# 07_-_HDMI.net
KiCad netlist of a schematic drawn in Altium Designer
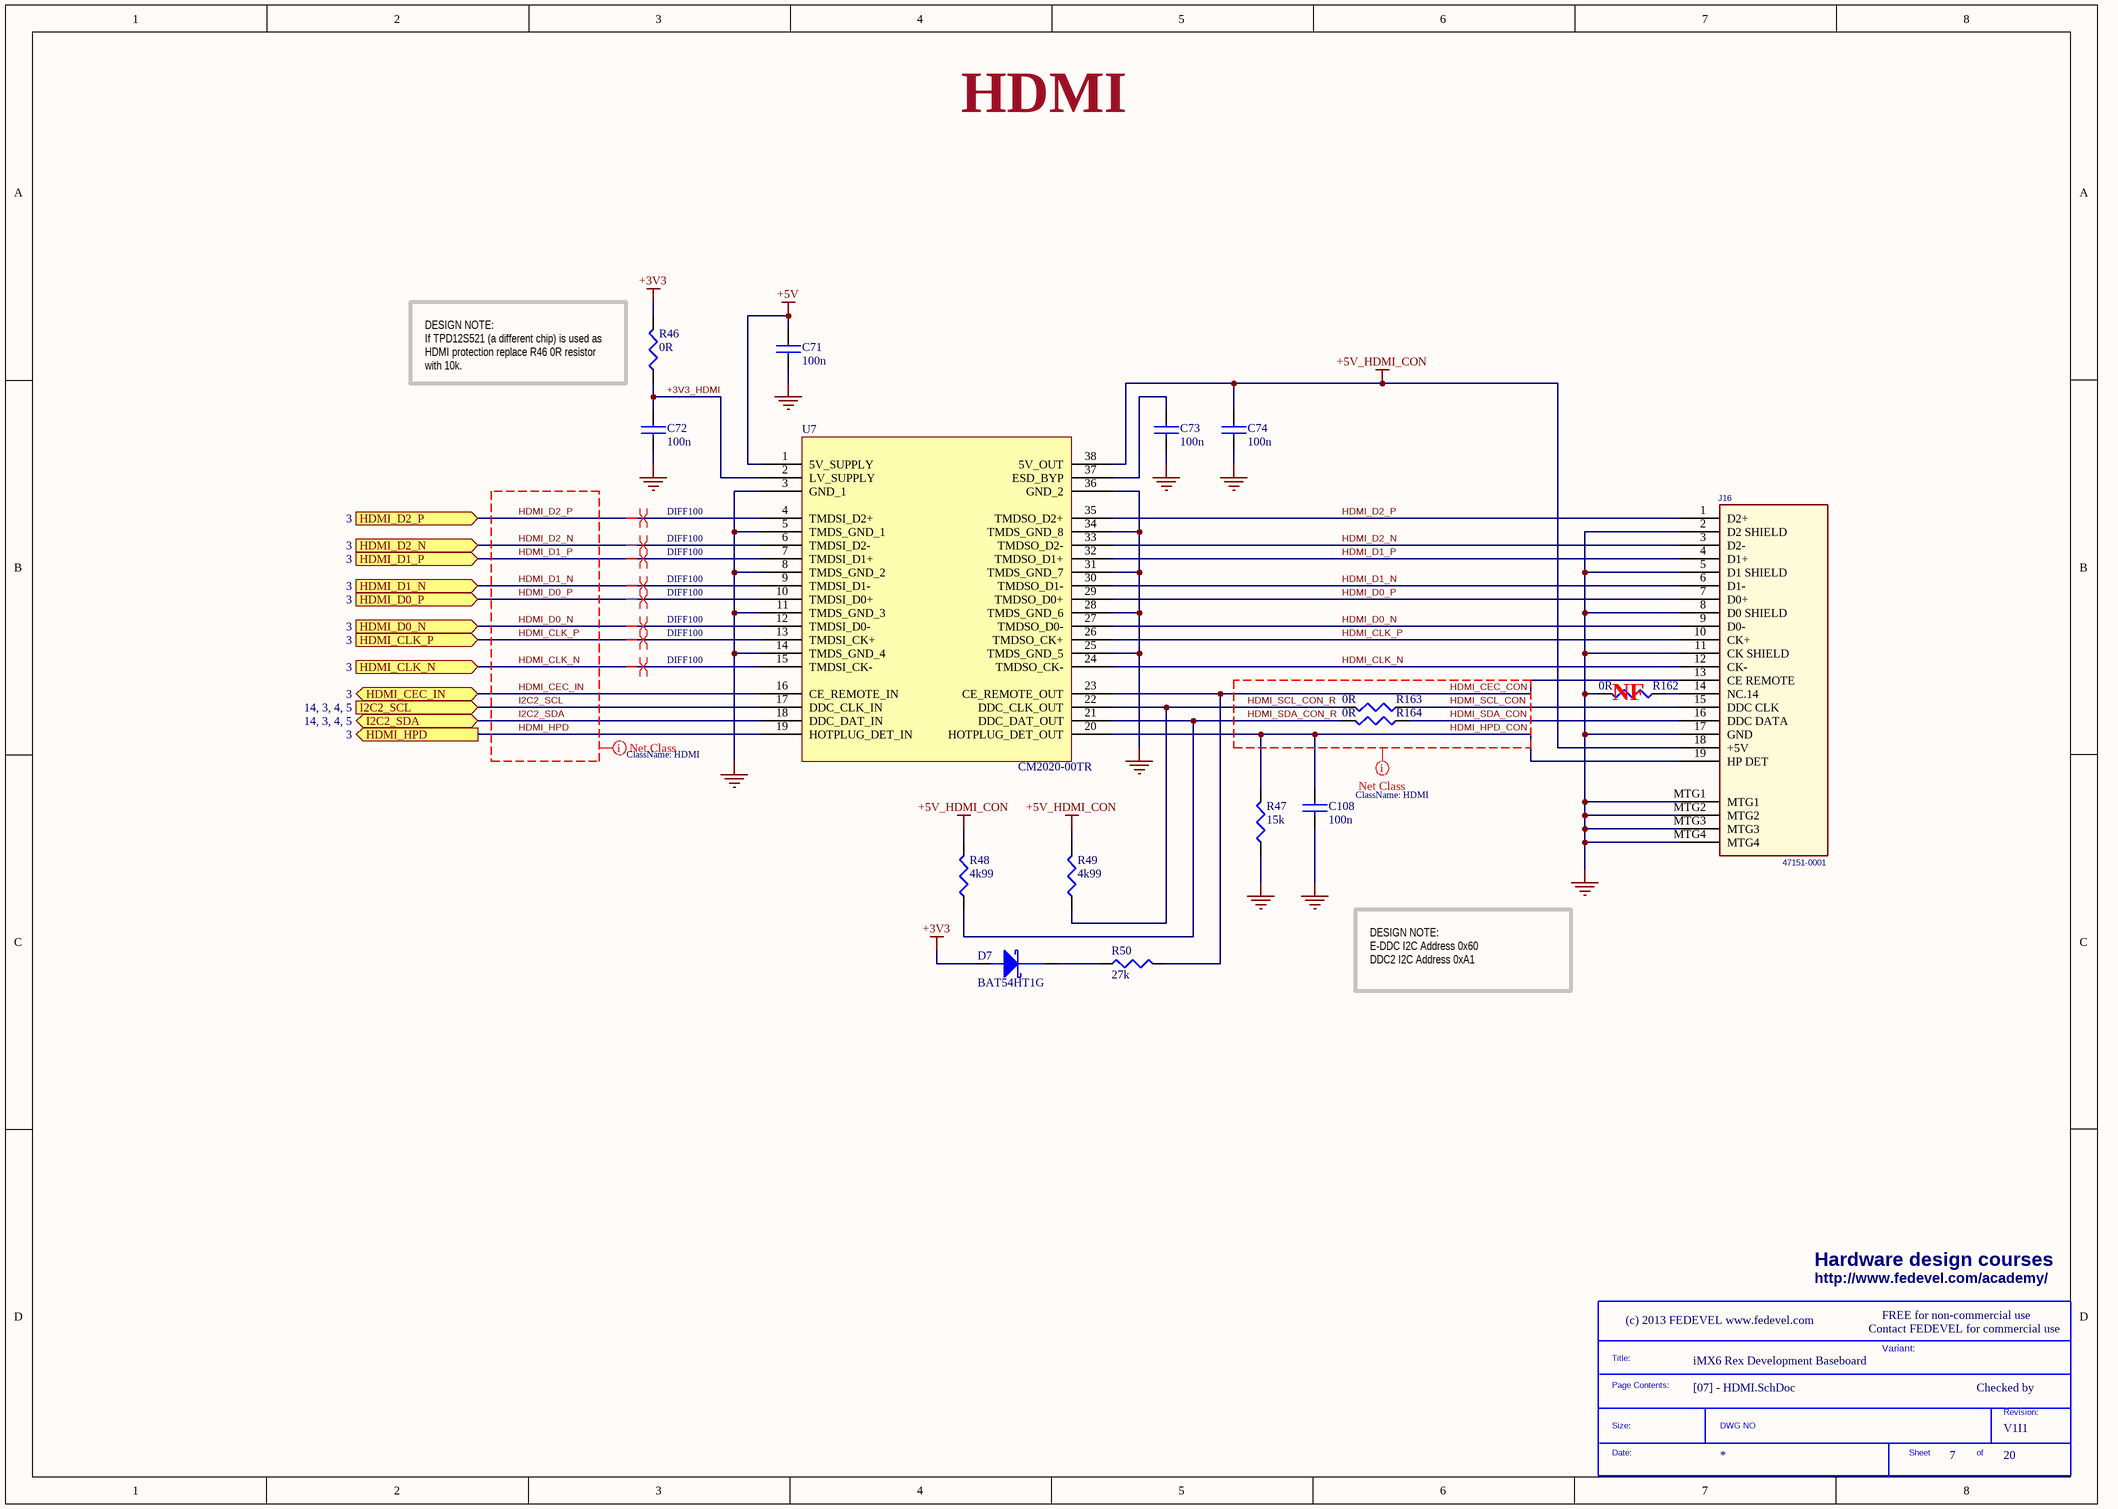
[diagram p0: [07] - HDMI.SchDoc]

(export (version "E")
  (design (tool "Eeschema 10.0.6"))
  (components
    (comp (ref "C71")
      (value "100n")
      (footprint "C0402")
      (description "CAP CER .10UF 50V X5R 10% 0402")
      (fields
        (field (name "MANUFACTURER") "TDK Corporation")
        (field (name "MANUFACTURER PART NUMBER") "C1005X5R1H104K")
      )
      (libsource (lib "Integrated_Library_RF_FEB_2012") (part "C1005X5R1H104K"))
    )
    (comp (ref "C72")
      (value "100n")
      (footprint "C0402")
      (description "CAP CER .10UF 50V X5R 10% 0402")
      (fields
        (field (name "MANUFACTURER") "TDK Corporation")
        (field (name "MANUFACTURER PART NUMBER") "C1005X5R1H104K")
      )
      (libsource (lib "Integrated_Library_RF_FEB_2012") (part "C1005X5R1H104K"))
    )
    (comp (ref "C73")
      (value "100n")
      (footprint "C0402")
      (description "CAP CER .10UF 50V X5R 10% 0402")
      (fields
        (field (name "MANUFACTURER") "TDK Corporation")
        (field (name "MANUFACTURER PART NUMBER") "C1005X5R1H104K")
      )
      (libsource (lib "Integrated_Library_RF_FEB_2012") (part "C1005X5R1H104K"))
    )
    (comp (ref "C74")
      (value "100n")
      (footprint "C0402")
      (description "CAP CER .10UF 50V X5R 10% 0402")
      (fields
        (field (name "MANUFACTURER") "TDK Corporation")
        (field (name "MANUFACTURER PART NUMBER") "C1005X5R1H104K")
      )
      (libsource (lib "Integrated_Library_RF_FEB_2012") (part "C1005X5R1H104K"))
    )
    (comp (ref "C108")
      (value "100n")
      (footprint "C0402")
      (description "CAP CER .10UF 50V X5R 10% 0402")
      (fields
        (field (name "MANUFACTURER") "TDK Corporation")
        (field (name "MANUFACTURER PART NUMBER") "C1005X5R1H104K")
      )
      (libsource (lib "Integrated_Library_RF_FEB_2012") (part "C1005X5R1H104K"))
    )
    (comp (ref "D7")
      (value "BAT54HT1G")
      (footprint "SOD323")
      (description "DIODE SCHOTTKY 30V 0.2A SOD323")
      (fields
        (field (name "MANUFACTURER") "Fairchild Semiconductor")
        (field (name ".CREATOR") "MM")
        (field (name ".CHECKED PCB") "RF, used by MM")
        (field (name ".CHECKED SCH") "MM")
      )
      (libsource (lib "Integrated_Library_RF_FEB_2012") (part "BAT54HT1G"))
    )
    (comp (ref "J16")
      (value "47151-0001")
      (footprint "HDMI")
      (description "CONN RCPT 19POS HDMI RT ANG SMD")
      (fields (field (name "MANUFACTURER") "Molex Connector Corporation"))
      (libsource (lib "Integrated_Library_RF_FEB_2012") (part "47151-0001"))
    )
    (comp (ref "R46")
      (value "0R")
      (footprint "R0402")
      (description "RES 0.0 OHM 1/16W 0402 SMD")
      (fields
        (field (name "MANUFACTURER") "Yageo")
        (field (name "MANUFACTURER PART NUMBER") "RC0402JR-070RL")
      )
      (libsource (lib "Integrated_Library_RF_FEB_2012") (part "RC0402JR-070RL"))
    )
    (comp (ref "R47")
      (value "15k")
      (footprint "R0402")
      (description "RES 15.0K OHM 1/16W 1% 0402 SMD")
      (fields
        (field (name "MANUFACTURER") "Yageo")
        (field (name "MANUFACTURER PART NUMBER") "RC0402FR-0715KL")
      )
      (libsource (lib "Integrated_Library_RF_FEB_2012") (part "RC0402FR-0715KL"))
    )
    (comp (ref "R48")
      (value "4k99")
      (footprint "R0402")
      (description "RES TF 4.99K OHM 1% 1/16W 0402")
      (fields
        (field (name "MANUFACTURER") "Stackpole Electronics Inc")
        (field (name "MANUFACTURER PART NUMBER") "RMCF0402FT4K99")
      )
      (libsource (lib "Integrated_Library_RF_FEB_2012") (part "RMCF0402FT4K99"))
    )
    (comp (ref "R49")
      (value "4k99")
      (footprint "R0402")
      (description "RES TF 4.99K OHM 1% 1/16W 0402")
      (fields
        (field (name "MANUFACTURER") "Stackpole Electronics Inc")
        (field (name "MANUFACTURER PART NUMBER") "RMCF0402FT4K99")
      )
      (libsource (lib "Integrated_Library_RF_FEB_2012") (part "RMCF0402FT4K99"))
    )
    (comp (ref "R50")
      (value "27k")
      (footprint "R0402")
      (description "RES 27.0K OHM 1/16W 1% 0402 SMD")
      (fields
        (field (name "MANUFACTURER") "Yageo")
        (field (name "MANUFACTURER PART NUMBER") "RC0402FR-0727KL")
        (field (name ".CHECKED PCB") "RF")
        (field (name ".CHECKED SCH") "RF")
      )
      (libsource (lib "Integrated_Library_RF_FEB_2012") (part "RC0402FR-0727KL"))
    )
    (comp (ref "R162")
      (value "0R")
      (footprint "R0402")
      (description "RES 0.0 OHM 1/16W 0402 SMD")
      (fields
        (field (name "MANUFACTURER") "Yageo")
        (field (name "MANUFACTURER PART NUMBER") "RC0402JR-070RL")
      )
      (libsource (lib "Integrated_Library_RF_FEB_2012") (part "RC0402JR-070RL"))
    )
    (comp (ref "R163")
      (value "0R")
      (footprint "R0402")
      (description "RES 0.0 OHM 1/16W 0402 SMD")
      (fields
        (field (name "MANUFACTURER") "Yageo")
        (field (name "MANUFACTURER PART NUMBER") "RC0402JR-070RL")
      )
      (libsource (lib "Integrated_Library_RF_FEB_2012") (part "RC0402JR-070RL"))
    )
    (comp (ref "R164")
      (value "0R")
      (footprint "R0402")
      (description "RES 0.0 OHM 1/16W 0402 SMD")
      (fields
        (field (name "MANUFACTURER") "Yageo")
        (field (name "MANUFACTURER PART NUMBER") "RC0402JR-070RL")
      )
      (libsource (lib "Integrated_Library_RF_FEB_2012") (part "RC0402JR-070RL"))
    )
    (comp (ref "U7")
      (value "CM2020-00TR")
      (footprint "TSSOP_38")
      (description "IC HDMI TX PORT P/I 38-TSSOP")
      (fields
        (field (name "MANUFACTURER") "ON Semiconductor")
        (field (name ".CREATOR") "MM")
        (field (name ".CHECKED PCB") "RF, used by MM")
        (field (name ".CHECKED SCH") "RF, used by MM")
      )
      (libsource (lib "Integrated_Library_RF_FEB_2012") (part "CM2020-00TR"))
    )
  )
  (nets
    (net (code "1") (name "+3V3") (class "Default")
      (node (ref "D7") (pin "2") (pinfunction "Anode_2") (pintype "passive"))
      (node (ref "R46") (pin "2") (pinfunction "2_2") (pintype "passive"))
    )
    (net (code "2") (name "+5V") (class "Default")
      (node (ref "C71") (pin "1") (pinfunction "1_1") (pintype "passive"))
      (node (ref "U7") (pin "1") (pinfunction "5V_SUPPLY_1") (pintype "passive"))
    )
    (net (code "3") (name "+5V_HDMI_CON") (class "Default")
      (node (ref "C74") (pin "1") (pinfunction "1_1") (pintype "passive"))
      (node (ref "J16") (pin "18") (pinfunction "+5V_18") (pintype "passive"))
      (node (ref "R48") (pin "2") (pinfunction "2_2") (pintype "passive"))
      (node (ref "R49") (pin "2") (pinfunction "2_2") (pintype "passive"))
      (node (ref "U7") (pin "38") (pinfunction "5V_OUT_38") (pintype "passive"))
    )
    (net (code "4") (name "/+3V3_HDMI") (class "Default")
      (node (ref "C72") (pin "1") (pinfunction "1_1") (pintype "passive"))
      (node (ref "R46") (pin "1") (pinfunction "1_1") (pintype "passive"))
      (node (ref "U7") (pin "2") (pinfunction "LV_SUPPLY_2") (pintype "passive"))
    )
    (net (code "5") (name "/HDMI_CEC_CON") (class "Default")
      (node (ref "J16") (pin "13") (pinfunction "CE_REMOTE_13") (pintype "passive"))
      (node (ref "R50") (pin "2") (pinfunction "2_2") (pintype "passive"))
      (node (ref "U7") (pin "23") (pinfunction "CE_REMOTE_OUT_23") (pintype "passive"))
    )
    (net (code "6") (name "/HDMI_CEC_IN") (class "Default")
      (node (ref "U7") (pin "16") (pinfunction "CE_REMOTE_IN_16") (pintype "passive"))
    )
    (net (code "7") (name "/HDMI_CLK_N") (class "Default")
      (node (ref "J16") (pin "12") (pinfunction "CK-_12") (pintype "passive"))
      (node (ref "U7") (pin "15") (pinfunction "TMDSI_CK-_15") (pintype "passive"))
      (node (ref "U7") (pin "24") (pinfunction "TMDSO_CK-_24") (pintype "passive"))
    )
    (net (code "8") (name "/HDMI_CLK_P") (class "Default")
      (node (ref "J16") (pin "10") (pinfunction "CK+_10") (pintype "passive"))
      (node (ref "U7") (pin "13") (pinfunction "TMDSI_CK+_13") (pintype "passive"))
      (node (ref "U7") (pin "26") (pinfunction "TMDSO_CK+_26") (pintype "passive"))
    )
    (net (code "9") (name "/HDMI_D0_N") (class "Default")
      (node (ref "J16") (pin "9") (pinfunction "D0-_9") (pintype "passive"))
      (node (ref "U7") (pin "12") (pinfunction "TMDSI_D0-_12") (pintype "passive"))
      (node (ref "U7") (pin "27") (pinfunction "TMDSO_D0-_27") (pintype "passive"))
    )
    (net (code "10") (name "/HDMI_D0_P") (class "Default")
      (node (ref "J16") (pin "7") (pinfunction "D0+_7") (pintype "passive"))
      (node (ref "U7") (pin "10") (pinfunction "TMDSI_D0+_10") (pintype "passive"))
      (node (ref "U7") (pin "29") (pinfunction "TMDSO_D0+_29") (pintype "passive"))
    )
    (net (code "11") (name "/HDMI_D1_N") (class "Default")
      (node (ref "J16") (pin "6") (pinfunction "D1-_6") (pintype "passive"))
      (node (ref "U7") (pin "30") (pinfunction "TMDSO_D1-_30") (pintype "passive"))
      (node (ref "U7") (pin "9") (pinfunction "TMDSI_D1-_9") (pintype "passive"))
    )
    (net (code "12") (name "/HDMI_D1_P") (class "Default")
      (node (ref "J16") (pin "4") (pinfunction "D1+_4") (pintype "passive"))
      (node (ref "U7") (pin "32") (pinfunction "TMDSO_D1+_32") (pintype "passive"))
      (node (ref "U7") (pin "7") (pinfunction "TMDSI_D1+_7") (pintype "passive"))
    )
    (net (code "13") (name "/HDMI_D2_N") (class "Default")
      (node (ref "J16") (pin "3") (pinfunction "D2-_3") (pintype "passive"))
      (node (ref "U7") (pin "33") (pinfunction "TMDSO_D2-_33") (pintype "passive"))
      (node (ref "U7") (pin "6") (pinfunction "TMDSI_D2-_6") (pintype "passive"))
    )
    (net (code "14") (name "/HDMI_D2_P") (class "Default")
      (node (ref "J16") (pin "1") (pinfunction "D2+_1") (pintype "passive"))
      (node (ref "U7") (pin "35") (pinfunction "TMDSO_D2+_35") (pintype "passive"))
      (node (ref "U7") (pin "4") (pinfunction "TMDSI_D2+_4") (pintype "passive"))
    )
    (net (code "15") (name "/HDMI_HPD") (class "Default")
      (node (ref "U7") (pin "19") (pinfunction "HOTPLUG_DET_IN_19") (pintype "passive"))
    )
    (net (code "16") (name "/HDMI_HPD_CON") (class "Default")
      (node (ref "C108") (pin "1") (pinfunction "1_1") (pintype "passive"))
      (node (ref "J16") (pin "19") (pinfunction "HP_DET_19") (pintype "passive"))
      (node (ref "R47") (pin "2") (pinfunction "2_2") (pintype "passive"))
      (node (ref "U7") (pin "20") (pinfunction "HOTPLUG_DET_OUT_20") (pintype "passive"))
    )
    (net (code "17") (name "/HDMI_SCL_CON") (class "Default")
      (node (ref "J16") (pin "15") (pinfunction "DDC_CLK_15") (pintype "passive"))
      (node (ref "R163") (pin "1") (pinfunction "1_1") (pintype "passive"))
    )
    (net (code "18") (name "/HDMI_SCL_CON_R") (class "Default")
      (node (ref "R163") (pin "2") (pinfunction "2_2") (pintype "passive"))
      (node (ref "R49") (pin "1") (pinfunction "1_1") (pintype "passive"))
      (node (ref "U7") (pin "22") (pinfunction "DDC_CLK_OUT_22") (pintype "passive"))
    )
    (net (code "19") (name "/HDMI_SDA_CON") (class "Default")
      (node (ref "J16") (pin "16") (pinfunction "DDC_DATA_16") (pintype "passive"))
      (node (ref "R164") (pin "1") (pinfunction "1_1") (pintype "passive"))
    )
    (net (code "20") (name "/HDMI_SDA_CON_R") (class "Default")
      (node (ref "R164") (pin "2") (pinfunction "2_2") (pintype "passive"))
      (node (ref "R48") (pin "1") (pinfunction "1_1") (pintype "passive"))
      (node (ref "U7") (pin "21") (pinfunction "DDC_DAT_OUT_21") (pintype "passive"))
    )
    (net (code "21") (name "/I2C2_SCL") (class "Default")
      (node (ref "U7") (pin "17") (pinfunction "DDC_CLK_IN_17") (pintype "passive"))
    )
    (net (code "22") (name "/I2C2_SDA") (class "Default")
      (node (ref "U7") (pin "18") (pinfunction "DDC_DAT_IN_18") (pintype "passive"))
    )
    (net (code "23") (name "GND") (class "Default")
      (node (ref "C108") (pin "2") (pinfunction "2_2") (pintype "passive"))
      (node (ref "C71") (pin "2") (pinfunction "2_2") (pintype "passive"))
      (node (ref "C72") (pin "2") (pinfunction "2_2") (pintype "passive"))
      (node (ref "C73") (pin "2") (pinfunction "2_2") (pintype "passive"))
      (node (ref "C74") (pin "2") (pinfunction "2_2") (pintype "passive"))
      (node (ref "J16") (pin "11") (pinfunction "CK_SHIELD_11") (pintype "passive"))
      (node (ref "J16") (pin "17") (pinfunction "GND_17") (pintype "passive"))
      (node (ref "J16") (pin "2") (pinfunction "D2_SHIELD_2") (pintype "passive"))
      (node (ref "J16") (pin "5") (pinfunction "D1_SHIELD_5") (pintype "passive"))
      (node (ref "J16") (pin "8") (pinfunction "D0_SHIELD_8") (pintype "passive"))
      (node (ref "J16") (pin "MTG1") (pinfunction "MTG1_MTG1") (pintype "passive"))
      (node (ref "J16") (pin "MTG2") (pinfunction "MTG2_MTG2") (pintype "passive"))
      (node (ref "J16") (pin "MTG3") (pinfunction "MTG3_MTG3") (pintype "passive"))
      (node (ref "J16") (pin "MTG4") (pinfunction "MTG4_MTG4") (pintype "passive"))
      (node (ref "R162") (pin "2") (pinfunction "2_2") (pintype "passive"))
      (node (ref "R47") (pin "1") (pinfunction "1_1") (pintype "passive"))
      (node (ref "U7") (pin "11") (pinfunction "TMDS_GND_3_11") (pintype "passive"))
      (node (ref "U7") (pin "14") (pinfunction "TMDS_GND_4_14") (pintype "passive"))
      (node (ref "U7") (pin "25") (pinfunction "TMDS_GND_5_25") (pintype "passive"))
      (node (ref "U7") (pin "28") (pinfunction "TMDS_GND_6_28") (pintype "passive"))
      (node (ref "U7") (pin "3") (pinfunction "GND_1_3") (pintype "passive"))
      (node (ref "U7") (pin "31") (pinfunction "TMDS_GND_7_31") (pintype "passive"))
      (node (ref "U7") (pin "34") (pinfunction "TMDS_GND_8_34") (pintype "passive"))
      (node (ref "U7") (pin "36") (pinfunction "GND_2_36") (pintype "passive"))
      (node (ref "U7") (pin "5") (pinfunction "TMDS_GND_1_5") (pintype "passive"))
      (node (ref "U7") (pin "8") (pinfunction "TMDS_GND_2_8") (pintype "passive"))
    )
    (net (code "24") (name "Net-(D7-Cathode)") (class "Default")
      (node (ref "D7") (pin "1") (pinfunction "Cathode_1") (pintype "passive"))
      (node (ref "R50") (pin "1") (pinfunction "1_1") (pintype "passive"))
    )
    (net (code "25") (name "Net-(J16-NC.14)") (class "Default")
      (node (ref "J16") (pin "14") (pinfunction "NC.14_14") (pintype "passive"))
      (node (ref "R162") (pin "1") (pinfunction "1_1") (pintype "passive"))
    )
    (net (code "26") (name "Net-(U7-ESD_BYP)") (class "Default")
      (node (ref "C73") (pin "1") (pinfunction "1_1") (pintype "passive"))
      (node (ref "U7") (pin "37") (pinfunction "ESD_BYP_37") (pintype "passive"))
    )
  )
)
